# PCA9546_Breakout.net
KiCad netlist of a schematic drawn in EAGLE
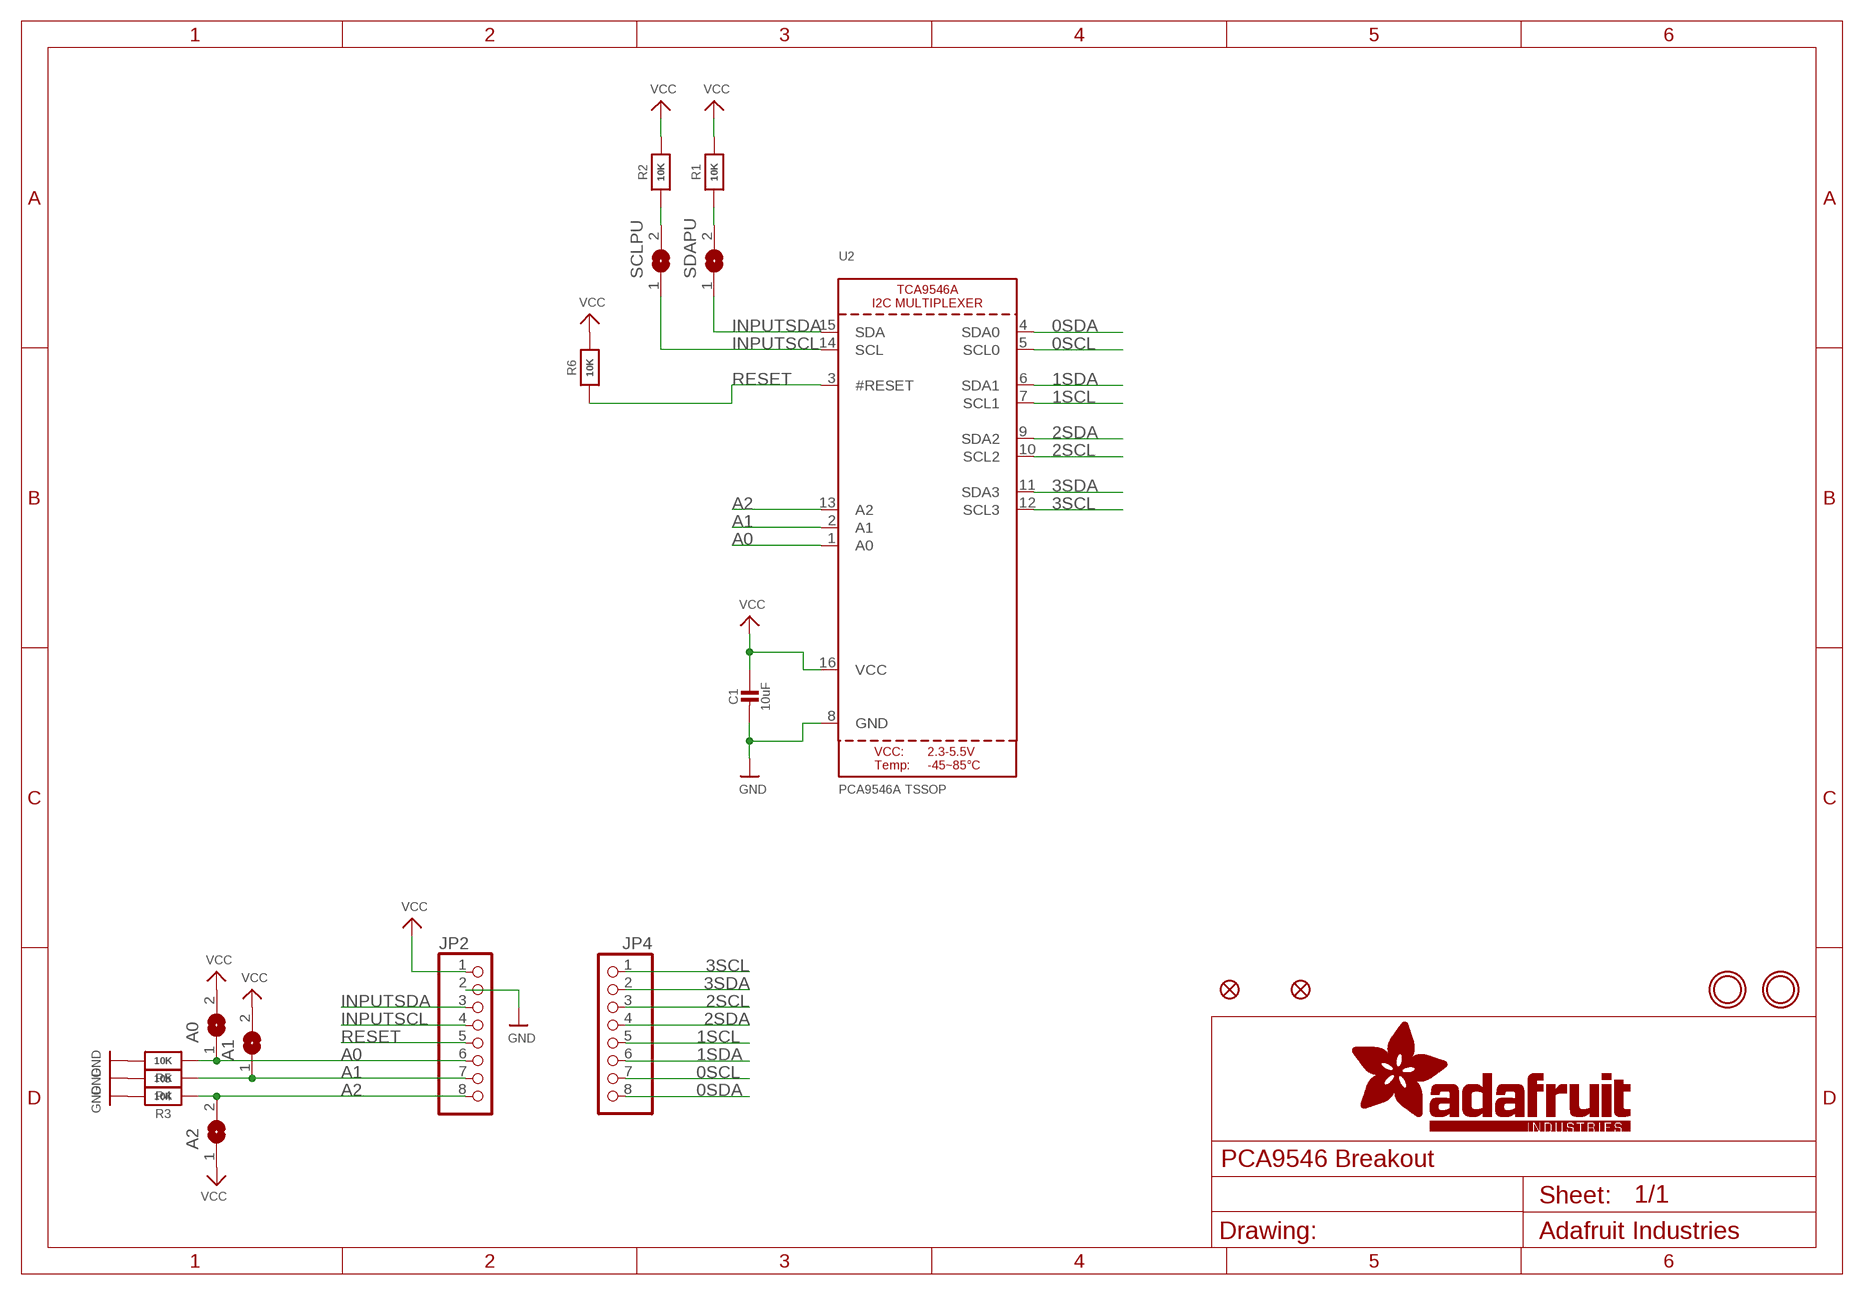
[diagram p0: schematic, sheet 1]

(export (version "E")
  (design (tool "Eeschema 10.0.6"))
  (components
    (comp (ref "A0")
      (value "SOLDERJUMPER")
      (footprint "eagle-import:SOLDERJUMPER_ARROW_NOPASTE")
      (libsource (lib "eagle-import") (part "SOLDERJUMPER"))
    )
    (comp (ref "A1")
      (value "SOLDERJUMPER")
      (footprint "eagle-import:SOLDERJUMPER_ARROW_NOPASTE")
      (libsource (lib "eagle-import") (part "SOLDERJUMPER"))
    )
    (comp (ref "A2")
      (value "SOLDERJUMPER")
      (footprint "eagle-import:SOLDERJUMPER_ARROW_NOPASTE")
      (libsource (lib "eagle-import") (part "SOLDERJUMPER"))
    )
    (comp (ref "C1")
      (value "10uF")
      (footprint "eagle-import:0805-NO")
      (libsource (lib "eagle-import") (part "CAP_CERAMIC0805-NOOUTLINE"))
    )
    (comp (ref "FID1")
      (value "FIDUCIAL_1MM")
      (footprint "eagle-import:FIDUCIAL_1MM")
      (libsource (lib "eagle-import") (part "FIDUCIAL_1MM"))
    )
    (comp (ref "FID3")
      (value "FIDUCIAL_1MM")
      (footprint "eagle-import:FIDUCIAL_1MM")
      (libsource (lib "eagle-import") (part "FIDUCIAL_1MM"))
    )
    (comp (ref "JP2")
      (value "HEADER-1X870MIL")
      (footprint "eagle-import:1X08_ROUND_70")
      (libsource (lib "eagle-import") (part "HEADER-1X870MIL"))
    )
    (comp (ref "JP4")
      (value "HEADER-1X870MIL")
      (footprint "eagle-import:1X08_ROUND_70")
      (libsource (lib "eagle-import") (part "HEADER-1X870MIL"))
    )
    (comp (ref "R1")
      (value "10K")
      (footprint "eagle-import:0603-NO")
      (libsource (lib "eagle-import") (part "RESISTOR_0603_NOOUT"))
    )
    (comp (ref "R2")
      (value "10K")
      (footprint "eagle-import:0603-NO")
      (libsource (lib "eagle-import") (part "RESISTOR_0603_NOOUT"))
    )
    (comp (ref "R3")
      (value "10K")
      (footprint "eagle-import:0603-NO")
      (libsource (lib "eagle-import") (part "RESISTOR_0603_NOOUT"))
    )
    (comp (ref "R4")
      (value "10K")
      (footprint "eagle-import:0603-NO")
      (libsource (lib "eagle-import") (part "RESISTOR_0603_NOOUT"))
    )
    (comp (ref "R5")
      (value "10K")
      (footprint "eagle-import:0603-NO")
      (libsource (lib "eagle-import") (part "RESISTOR_0603_NOOUT"))
    )
    (comp (ref "R6")
      (value "10K")
      (footprint "eagle-import:0603-NO")
      (libsource (lib "eagle-import") (part "RESISTOR_0603_NOOUT"))
    )
    (comp (ref "SCLPU")
      (value "SOLDERJUMPERCLOSED")
      (footprint "eagle-import:SOLDERJUMPER_CLOSEDWIRE")
      (libsource (lib "eagle-import") (part "SOLDERJUMPERCLOSED"))
    )
    (comp (ref "SDAPU")
      (value "SOLDERJUMPERCLOSED")
      (footprint "eagle-import:SOLDERJUMPER_CLOSEDWIRE")
      (libsource (lib "eagle-import") (part "SOLDERJUMPERCLOSED"))
    )
    (comp (ref "U$4")
      (value "MOUNTINGHOLE2.5")
      (footprint "eagle-import:MOUNTINGHOLE_2.5_PLATED")
      (libsource (lib "eagle-import") (part "MOUNTINGHOLE2.5"))
    )
    (comp (ref "U$5")
      (value "MOUNTINGHOLE2.5")
      (footprint "eagle-import:MOUNTINGHOLE_2.5_PLATED")
      (libsource (lib "eagle-import") (part "MOUNTINGHOLE2.5"))
    )
    (comp (ref "U2")
      (value "PCA9546A TSSOP")
      (footprint "eagle-import:TSSOP16")
      (libsource (lib "eagle-import") (part "XCA9546APW"))
    )
  )
  (nets
    (net (code "1") (name "/0SCL") (class "Default")
      (node (ref "JP4") (pin "7") (pinfunction "7_7") (pintype "passive"))
      (node (ref "U2") (pin "5") (pinfunction "SCL0_5") (pintype "bidirectional"))
    )
    (net (code "2") (name "/0SDA") (class "Default")
      (node (ref "JP4") (pin "8") (pinfunction "8_8") (pintype "passive"))
      (node (ref "U2") (pin "4") (pinfunction "SDA0_4") (pintype "bidirectional"))
    )
    (net (code "3") (name "/1SCL") (class "Default")
      (node (ref "JP4") (pin "5") (pinfunction "5_5") (pintype "passive"))
      (node (ref "U2") (pin "7") (pinfunction "SCL1_7") (pintype "bidirectional"))
    )
    (net (code "4") (name "/1SDA") (class "Default")
      (node (ref "JP4") (pin "6") (pinfunction "6_6") (pintype "passive"))
      (node (ref "U2") (pin "6") (pinfunction "SDA1_6") (pintype "bidirectional"))
    )
    (net (code "5") (name "/2SCL") (class "Default")
      (node (ref "JP4") (pin "3") (pinfunction "3_3") (pintype "passive"))
      (node (ref "U2") (pin "10") (pinfunction "SCL2_10") (pintype "bidirectional"))
    )
    (net (code "6") (name "/2SDA") (class "Default")
      (node (ref "JP4") (pin "4") (pinfunction "4_4") (pintype "passive"))
      (node (ref "U2") (pin "9") (pinfunction "SDA2_9") (pintype "bidirectional"))
    )
    (net (code "7") (name "/3SCL") (class "Default")
      (node (ref "JP4") (pin "1") (pinfunction "1_1") (pintype "passive"))
      (node (ref "U2") (pin "12") (pinfunction "SCL3_12") (pintype "bidirectional"))
    )
    (net (code "8") (name "/3SDA") (class "Default")
      (node (ref "JP4") (pin "2") (pinfunction "2_2") (pintype "passive"))
      (node (ref "U2") (pin "11") (pinfunction "SDA3_11") (pintype "bidirectional"))
    )
    (net (code "9") (name "/A0") (class "Default")
      (node (ref "A0") (pin "1") (pinfunction "1_1") (pintype "passive"))
      (node (ref "JP2") (pin "6") (pinfunction "6_6") (pintype "passive"))
      (node (ref "R5") (pin "1") (pinfunction "1_1") (pintype "passive"))
      (node (ref "U2") (pin "1") (pinfunction "A0_1") (pintype "bidirectional"))
    )
    (net (code "10") (name "/A1") (class "Default")
      (node (ref "A1") (pin "1") (pinfunction "1_1") (pintype "passive"))
      (node (ref "JP2") (pin "7") (pinfunction "7_7") (pintype "passive"))
      (node (ref "R4") (pin "1") (pinfunction "1_1") (pintype "passive"))
      (node (ref "U2") (pin "2") (pinfunction "A1_2") (pintype "bidirectional"))
    )
    (net (code "11") (name "/A2") (class "Default")
      (node (ref "A2") (pin "2") (pinfunction "2_2") (pintype "passive"))
      (node (ref "JP2") (pin "8") (pinfunction "8_8") (pintype "passive"))
      (node (ref "R3") (pin "1") (pinfunction "1_1") (pintype "passive"))
      (node (ref "U2") (pin "13") (pinfunction "A2_13") (pintype "bidirectional"))
    )
    (net (code "12") (name "/INPUTSCL") (class "Default")
      (node (ref "JP2") (pin "4") (pinfunction "4_4") (pintype "passive"))
      (node (ref "SCLPU") (pin "1") (pinfunction "1_1") (pintype "passive"))
      (node (ref "U2") (pin "14") (pinfunction "SCL_14") (pintype "bidirectional"))
    )
    (net (code "13") (name "/INPUTSDA") (class "Default")
      (node (ref "JP2") (pin "3") (pinfunction "3_3") (pintype "passive"))
      (node (ref "SDAPU") (pin "1") (pinfunction "1_1") (pintype "passive"))
      (node (ref "U2") (pin "15") (pinfunction "SDA_15") (pintype "bidirectional"))
    )
    (net (code "14") (name "/RESET") (class "Default")
      (node (ref "JP2") (pin "5") (pinfunction "5_5") (pintype "passive"))
      (node (ref "R6") (pin "1") (pinfunction "1_1") (pintype "passive"))
      (node (ref "U2") (pin "3") (pinfunction "#RESET_3") (pintype "bidirectional"))
    )
    (net (code "15") (name "GND") (class "Default")
      (node (ref "C1") (pin "2") (pinfunction "2_2") (pintype "passive"))
      (node (ref "JP2") (pin "2") (pinfunction "2_2") (pintype "passive"))
      (node (ref "R3") (pin "2") (pinfunction "2_2") (pintype "passive"))
      (node (ref "R4") (pin "2") (pinfunction "2_2") (pintype "passive"))
      (node (ref "R5") (pin "2") (pinfunction "2_2") (pintype "passive"))
      (node (ref "U2") (pin "8") (pinfunction "GND_8") (pintype "bidirectional"))
    )
    (net (code "16") (name "Net-(R1-Pad1)") (class "Default")
      (node (ref "R1") (pin "1") (pinfunction "1_1") (pintype "passive"))
      (node (ref "SDAPU") (pin "2") (pinfunction "2_2") (pintype "passive"))
    )
    (net (code "17") (name "Net-(R2-Pad1)") (class "Default")
      (node (ref "R2") (pin "1") (pinfunction "1_1") (pintype "passive"))
      (node (ref "SCLPU") (pin "2") (pinfunction "2_2") (pintype "passive"))
    )
    (net (code "18") (name "VCC") (class "Default")
      (node (ref "A0") (pin "2") (pinfunction "2_2") (pintype "passive"))
      (node (ref "A1") (pin "2") (pinfunction "2_2") (pintype "passive"))
      (node (ref "A2") (pin "1") (pinfunction "1_1") (pintype "passive"))
      (node (ref "C1") (pin "1") (pinfunction "1_1") (pintype "passive"))
      (node (ref "JP2") (pin "1") (pinfunction "1_1") (pintype "passive"))
      (node (ref "R1") (pin "2") (pinfunction "2_2") (pintype "passive"))
      (node (ref "R2") (pin "2") (pinfunction "2_2") (pintype "passive"))
      (node (ref "R6") (pin "2") (pinfunction "2_2") (pintype "passive"))
      (node (ref "U2") (pin "16") (pinfunction "VCC_16") (pintype "bidirectional"))
    )
  )
)
